# Sheet1.net
KiCad netlist of a schematic drawn in Altium Designer
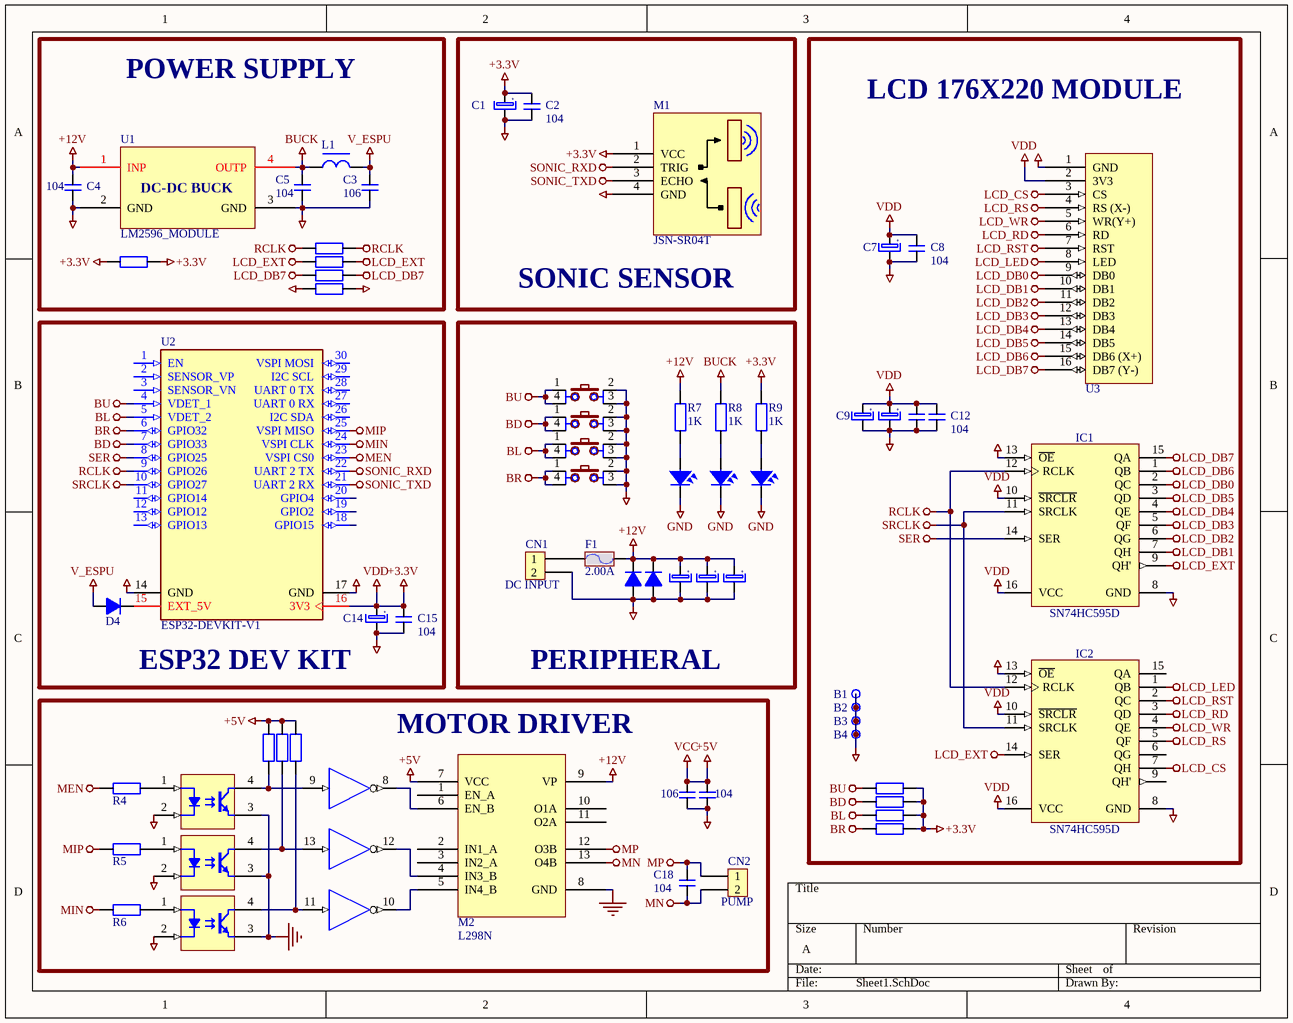
[diagram p0: Sheet1.SchDoc]

(export (version "E")
  (design (tool "Eeschema 10.0.6"))
  (components
    (comp (ref "B1")
      (value "Plated Hole")
      (footprint "MTG300_600")
      (description "Single Terminal Socket")
      (fields (field (name "PART NUMBER") "PLATED_HOLE3.0_PAD6.0") (field (name "AUTHOR") "CERN DEM JLC"))
      (libsource (lib "Eletro-mechanical") (part "Single Terminal Socket"))
    )
    (comp (ref "B2")
      (value "Plated Hole")
      (footprint "MTG300_600")
      (description "Single Terminal Socket")
      (fields (field (name "PART NUMBER") "PLATED_HOLE3.0_PAD6.0") (field (name "AUTHOR") "CERN DEM JLC"))
      (libsource (lib "Eletro-mechanical") (part "Single Terminal Socket"))
    )
    (comp (ref "B3")
      (value "Plated Hole")
      (footprint "MTG300_600")
      (description "Single Terminal Socket")
      (fields (field (name "PART NUMBER") "PLATED_HOLE3.0_PAD6.0") (field (name "AUTHOR") "CERN DEM JLC"))
      (libsource (lib "Eletro-mechanical") (part "Single Terminal Socket"))
    )
    (comp (ref "B4")
      (value "Plated Hole")
      (footprint "MTG300_600")
      (description "Single Terminal Socket")
      (fields (field (name "PART NUMBER") "PLATED_HOLE3.0_PAD6.0") (field (name "AUTHOR") "CERN DEM JLC"))
      (libsource (lib "Eletro-mechanical") (part "Single Terminal Socket"))
    )
    (comp (ref "C1")
      (value "220uF")
      (footprint "Cap-P-2.5/5")
      (description "Polarized capacitor")
      (libsource (lib "Library") (part "Cap-Pol-Dip"))
    )
    (comp (ref "C2")
      (value "104")
      (footprint "Cap-Non-150mil")
      (description "Non-polar capacitor")
      (libsource (lib "Library") (part "Cap-Non-Dip"))
    )
    (comp (ref "C3")
      (value "106")
      (footprint "CAP-SMD-0805")
      (description "Non-polar capacitor")
      (libsource (lib "Library") (part "Cap-Non-SMD"))
    )
    (comp (ref "C4")
      (value "104")
      (footprint "Cap-Non-150mil")
      (description "Non-polar capacitor")
      (libsource (lib "Library") (part "Cap-Non-Dip"))
    )
    (comp (ref "C5")
      (value "104")
      (footprint "Cap-Non-150mil")
      (description "Non-polar capacitor")
      (libsource (lib "Library") (part "Cap-Non-Dip"))
    )
    (comp (ref "C6")
      (value "470uF")
      (footprint "Cap-P-3.8/6.3")
      (description "Polarized capacitor")
      (libsource (lib "Library") (part "Cap-Pol-Dip"))
    )
    (comp (ref "C7")
      (value "220uF")
      (footprint "Cap-P-2.5/5")
      (description "Polarized capacitor")
      (libsource (lib "Library") (part "Cap-Pol-Dip"))
    )
    (comp (ref "C8")
      (value "104")
      (footprint "Cap-Non-150mil")
      (description "Non-polar capacitor")
      (libsource (lib "Library") (part "Cap-Non-Dip"))
    )
    (comp (ref "C9")
      (value "220uF")
      (footprint "Cap-P-2.5/5")
      (description "Polarized capacitor")
      (libsource (lib "Library") (part "Cap-Pol-Dip"))
    )
    (comp (ref "C10")
      (value "220uF")
      (footprint "Cap-P-2.5/5")
      (description "Polarized capacitor")
      (libsource (lib "Library") (part "Cap-Pol-Dip"))
    )
    (comp (ref "C11")
      (value "104")
      (footprint "Cap-Non-150mil")
      (description "Non-polar capacitor")
      (libsource (lib "Library") (part "Cap-Non-Dip"))
    )
    (comp (ref "C12")
      (value "104")
      (footprint "Cap-Non-150mil")
      (description "Non-polar capacitor")
      (libsource (lib "Library") (part "Cap-Non-Dip"))
    )
    (comp (ref "C13")
      (value "470uF")
      (footprint "Cap-P-3.8/6.3")
      (description "Polarized capacitor")
      (libsource (lib "Library") (part "Cap-Pol-Dip"))
    )
    (comp (ref "C14")
      (value "220uF")
      (footprint "Cap-P-2.5/5")
      (description "Polarized capacitor")
      (libsource (lib "Library") (part "Cap-Pol-Dip"))
    )
    (comp (ref "C15")
      (value "104")
      (footprint "Cap-Non-150mil")
      (description "Non-polar capacitor")
      (libsource (lib "Library") (part "Cap-Non-Dip"))
    )
    (comp (ref "C16")
      (value "106")
      (footprint "CAP-SMD-0805")
      (description "Non-polar capacitor")
      (libsource (lib "Library") (part "Cap-Non-SMD"))
    )
    (comp (ref "C17")
      (value "104")
      (footprint "CAP-SMD-0805")
      (description "Non-polar capacitor")
      (libsource (lib "Library") (part "Cap-Non-SMD"))
    )
    (comp (ref "C18")
      (value "104")
      (footprint "CAP-SMD-0805")
      (description "Non-polar capacitor")
      (libsource (lib "Library") (part "Cap-Non-Dip"))
    )
    (comp (ref "C19")
      (value "470uF")
      (footprint "Cap-P-3.8/6.3")
      (description "Polarized capacitor")
      (libsource (lib "Library") (part "Cap-Pol-Dip"))
    )
    (comp (ref "CN1") (value "DC INPUT") (footprint "KF2/5.08") (libsource (lib "Library") (part "KF 2")))
    (comp (ref "CN2") (value "PUMP") (footprint "KF2/5.08") (libsource (lib "") (part "KF 2_1")))
    (comp (ref "D1")
      (value "SS14")
      (footprint "SOD 106")
      (description "Diode SMD")
      (libsource (lib "Library") (part "Diode SMD"))
    )
    (comp (ref "D2")
      (value "SS14")
      (footprint "SOD 106")
      (description "Diode SMD")
      (libsource (lib "Library") (part "Diode SMD"))
    )
    (comp (ref "D4")
      (value "SS14")
      (footprint "SOD 106")
      (description "Diode SMD")
      (libsource (lib "Library") (part "Diode SMD"))
    )
    (comp (ref "F1") (value "2.00A") (footprint "Fuse-Dip1") (libsource (lib "Library") (part "Fuse Dip")))
    (comp (ref "IC1")
      (value "SN74HC595D")
      (footprint "SOIC127P600X175-16N")
      (description "8-Bit Shift Register With 3-State Output Register")
      (fields (field (name "MANUFACTURER") "TEXAS INSTRUMENTS") (field (name "AUTHOR") "CERN DEM JLC"))
      (libsource (lib "ICs And Semiconductors") (part "74595"))
    )
    (comp (ref "IC2")
      (value "SN74HC595D")
      (footprint "SOIC127P600X175-16N")
      (description "8-Bit Shift Register With 3-State Output Register")
      (fields (field (name "MANUFACTURER") "TEXAS INSTRUMENTS") (field (name "AUTHOR") "CERN DEM JLC"))
      (libsource (lib "ICs And Semiconductors") (part "74595"))
    )
    (comp (ref "IC3")
      (value "FOD817DSD")
      (footprint "DIP4")
      (description "Single Optocoupler")
      (fields (field (name "MANUFACTURER") "FAIRCHILD SEMICONDUCTOR") (field (name "AUTHOR") "CERN DEM JLC"))
      (libsource (lib "ICs And Semiconductors") (part "Optocoupler Type7"))
    )
    (comp (ref "IC4")
      (value "FOD817DSD")
      (footprint "DIP4")
      (description "Single Optocoupler")
      (fields (field (name "MANUFACTURER") "FAIRCHILD SEMICONDUCTOR") (field (name "AUTHOR") "CERN DEM JLC"))
      (libsource (lib "ICs And Semiconductors") (part "Optocoupler Type7"))
    )
    (comp (ref "IC5")
      (value "FOD817DSD")
      (footprint "DIP4")
      (description "Single Optocoupler")
      (fields (field (name "MANUFACTURER") "FAIRCHILD SEMICONDUCTOR") (field (name "AUTHOR") "CERN DEM JLC"))
      (libsource (lib "ICs And Semiconductors") (part "Optocoupler Type7"))
    )
    (comp (ref "IC6")
      (value "74HC14D")
      (footprint "SOIC127P600X175-14N")
      (description "Hex Schmitt-Trigger Inverter")
      (fields (field (name "MANUFACTURER") "NXP SEMICONDUCTORS") (field (name "AUTHOR") "CERN DEM JLC"))
      (libsource (lib "ICs And Semiconductors") (part "7414"))
    )
    (comp (ref "L1")
      (value "470uH")
      (footprint "L-DIP-M-5.3")
      (description "Inductor")
      (libsource (lib "Library") (part "IND-DIP-1"))
    )
    (comp (ref "LED1") (value "POWER") (footprint "LED-0805") (libsource (lib "Library") (part "LED_SMD")))
    (comp (ref "LED2") (value "ESP-5.0V") (footprint "LED-0805") (libsource (lib "Library") (part "LED_SMD")))
    (comp (ref "LED3") (value "ESP-3.3V") (footprint "LED-0805") (libsource (lib "Library") (part "LED_SMD")))
    (comp (ref "M1")
      (value "JSN-SR04T")
      (footprint "JSN-SR04T")
      (libsource (lib "TOAN_VERSION_1_0") (part "JSN-SR04T"))
    )
    (comp (ref "M2")
      (value "L298N")
      (footprint "L298N_MODULE")
      (libsource (lib "TOAN_VERSION_1_0") (part "L298N"))
    )
    (comp (ref "R1")
      (value "1K")
      (footprint "RES-SMD-0805")
      (description "Resistor 1/4W")
      (libsource (lib "Library") (part "Res 1/4W"))
    )
    (comp (ref "R2")
      (value "1K")
      (footprint "RES-SMD-0805")
      (description "Resistor 1/4W")
      (libsource (lib "Library") (part "Res 1/4W"))
    )
    (comp (ref "R3")
      (value "1K")
      (footprint "RES-SMD-0805")
      (description "Resistor 1/4W")
      (libsource (lib "Library") (part "Res 1/4W"))
    )
    (comp (ref "R4")
      (value "1K")
      (footprint "RES-SMD-0805")
      (description "Resistor 1/4W")
      (libsource (lib "Library") (part "Res 1/4W"))
    )
    (comp (ref "R5")
      (value "1K")
      (footprint "RES-SMD-0805")
      (description "Resistor 1/4W")
      (libsource (lib "Library") (part "Res 1/4W"))
    )
    (comp (ref "R6")
      (value "1K")
      (footprint "RES-SMD-0805")
      (description "Resistor 1/4W")
      (libsource (lib "Library") (part "Res 1/4W"))
    )
    (comp (ref "R7")
      (value "1K")
      (footprint "RES-SMD-0805")
      (description "Resistor 1/4W")
      (libsource (lib "Library") (part "Res 1/4W"))
    )
    (comp (ref "R8")
      (value "1K")
      (footprint "RES-SMD-0805")
      (description "Resistor 1/4W")
      (libsource (lib "Library") (part "Res 1/4W"))
    )
    (comp (ref "R9")
      (value "1K")
      (footprint "RES-SMD-0805")
      (description "Resistor 1/4W")
      (libsource (lib "Library") (part "Res 1/4W"))
    )
    (comp (ref "R13")
      (value "0R")
      (footprint "RES-SMD-0805")
      (description "Resistor SMD")
      (libsource (lib "Library") (part "Res SMD"))
    )
    (comp (ref "R14")
      (value "0R")
      (footprint "RES-SMD-0805")
      (description "Resistor SMD")
      (libsource (lib "Library") (part "Res SMD"))
    )
    (comp (ref "R15")
      (value "0R")
      (footprint "RES-SMD-0805")
      (description "Resistor SMD")
      (libsource (lib "Library") (part "Res SMD"))
    )
    (comp (ref "R16")
      (value "0R")
      (footprint "RES-SMD-1206")
      (description "Resistor SMD")
      (libsource (lib "Library") (part "Res SMD"))
    )
    (comp (ref "R21")
      (value "1K")
      (footprint "RES-SMD-0805")
      (description "Resistor 1/4W")
      (libsource (lib "Library") (part "Res 1/4W"))
    )
    (comp (ref "R22")
      (value "1K")
      (footprint "RES-SMD-0805")
      (description "Resistor 1/4W")
      (libsource (lib "Library") (part "Res 1/4W"))
    )
    (comp (ref "R23")
      (value "1K")
      (footprint "RES-SMD-0805")
      (description "Resistor 1/4W")
      (libsource (lib "Library") (part "Res 1/4W"))
    )
    (comp (ref "R24")
      (value "1K")
      (footprint "RES-SMD-0805")
      (description "Resistor 1/4W")
      (libsource (lib "Library") (part "Res 1/4W"))
    )
    (comp (ref "R27")
      (value "0R")
      (footprint "RES-SMD-1206")
      (description "Resistor 1/4W")
      (libsource (lib "Library") (part "Res 1/4W"))
    )
    (comp (ref "SW1")
      (value "UP")
      (footprint "Button-Dip4/6x6")
      (description "Switch button 4 pin")
      (libsource (lib "Library") (part "Button-4"))
    )
    (comp (ref "SW2")
      (value "DOWN")
      (footprint "Button-Dip4/6x6")
      (description "Switch button 4 pin")
      (libsource (lib "Library") (part "Button-4"))
    )
    (comp (ref "SW3")
      (value "LEFT")
      (footprint "Button-Dip4/6x6")
      (description "Switch button 4 pin")
      (libsource (lib "Library") (part "Button-4"))
    )
    (comp (ref "SW4")
      (value "RIGHT")
      (footprint "Button-Dip4/6x6")
      (description "Switch button 4 pin")
      (libsource (lib "Library") (part "Button-4"))
    )
    (comp (ref "U1")
      (value "LM2596_MODULE")
      (footprint "LM2596_MODULE")
      (libsource (lib "TOAN_VERSION_1_0") (part "LM2596_MODULE"))
    )
    (comp (ref "U2")
      (value "ESP32-DEVKIT-V1")
      (footprint "MODULE_ESP32-DEVKITC-32D")
      (fields (field (name "MF") "Espressif Systems") (field (name "MP") "ESP32-DEVKITC-32D"))
      (libsource (lib "TOAN_VERSION_1_0") (part "ESP32-DEVKIT-V1"))
    )
    (comp (ref "U3")
      (value "ST7775R_2.0")
      (footprint "LCD_176X220_MODULE")
      (libsource (lib "TOAN_VERSION_1_0") (part "LCD_176x220_ST7775R"))
    )
  )
  (nets
    (net (code "1") (name "+3.3V") (class "Default")
      (node (ref "C1") (pin "1") (pinfunction "1_1") (pintype "passive"))
      (node (ref "C10") (pin "1") (pinfunction "1_1") (pintype "passive"))
      (node (ref "C11") (pin "2") (pinfunction "2_2") (pintype "passive"))
      (node (ref "C12") (pin "2") (pinfunction "2_2") (pintype "passive"))
      (node (ref "C14") (pin "1") (pinfunction "1_1") (pintype "passive"))
      (node (ref "C15") (pin "2") (pinfunction "2_2") (pintype "passive"))
      (node (ref "C2") (pin "2") (pinfunction "2_2") (pintype "passive"))
      (node (ref "C7") (pin "1") (pinfunction "1_1") (pintype "passive"))
      (node (ref "C8") (pin "2") (pinfunction "2_2") (pintype "passive"))
      (node (ref "C9") (pin "1") (pinfunction "1_1") (pintype "passive"))
      (node (ref "IC1") (pin "10") (pinfunction "~{SRCLR}_10") (pintype "input"))
      (node (ref "IC1") (pin "16") (pinfunction "VCC_16") (pintype "power_in"))
      (node (ref "IC2") (pin "10") (pinfunction "~{SRCLR}_10") (pintype "input"))
      (node (ref "IC2") (pin "16") (pinfunction "VCC_16") (pintype "power_in"))
      (node (ref "M1") (pin "1") (pinfunction "VCC_1") (pintype "passive"))
      (node (ref "R21") (pin "1") (pinfunction "1_1") (pintype "passive"))
      (node (ref "R22") (pin "1") (pinfunction "1_1") (pintype "passive"))
      (node (ref "R23") (pin "1") (pinfunction "1_1") (pintype "passive"))
      (node (ref "R24") (pin "1") (pinfunction "1_1") (pintype "passive"))
      (node (ref "R27") (pin "1") (pinfunction "1_1") (pintype "passive"))
      (node (ref "R27") (pin "2") (pinfunction "2_2") (pintype "passive"))
      (node (ref "R9") (pin "2") (pinfunction "2_2") (pintype "passive"))
      (node (ref "U2") (pin "16") (pinfunction "3V3_16") (pintype "power_in"))
      (node (ref "U3") (pin "2") (pinfunction "3V3_2") (pintype "power_in"))
    )
    (net (code "2") (name "+5V") (class "Default")
      (node (ref "C16") (pin "2") (pinfunction "2_2") (pintype "passive"))
      (node (ref "C17") (pin "2") (pinfunction "2_2") (pintype "passive"))
      (node (ref "IC6") (pin "14") (pinfunction "VCC_14") (pintype "power_in"))
      (node (ref "M2") (pin "7") (pinfunction "VCC_7") (pintype "passive"))
      (node (ref "R1") (pin "2") (pinfunction "2_2") (pintype "passive"))
      (node (ref "R2") (pin "2") (pinfunction "2_2") (pintype "passive"))
      (node (ref "R3") (pin "2") (pinfunction "2_2") (pintype "passive"))
    )
    (net (code "3") (name "+12V") (class "Default")
      (node (ref "C13") (pin "1") (pinfunction "1_1") (pintype "passive"))
      (node (ref "C19") (pin "1") (pinfunction "1_1") (pintype "passive"))
      (node (ref "C4") (pin "1") (pinfunction "1_1") (pintype "passive"))
      (node (ref "C6") (pin "1") (pinfunction "1_1") (pintype "passive"))
      (node (ref "D1") (pin "2") (pinfunction "K_2") (pintype "passive"))
      (node (ref "D2") (pin "2") (pinfunction "K_2") (pintype "passive"))
      (node (ref "F1") (pin "2") (pinfunction "2_2") (pintype "passive"))
      (node (ref "M2") (pin "9") (pinfunction "VP_9") (pintype "passive"))
      (node (ref "R7") (pin "2") (pinfunction "2_2") (pintype "passive"))
      (node (ref "U1") (pin "1") (pinfunction "INP_1") (pintype "power_in"))
    )
    (net (code "4") (name "BD") (class "Default")
      (node (ref "R24") (pin "2") (pinfunction "2_2") (pintype "passive"))
      (node (ref "SW2") (pin "1") (pintype "passive"))
      (node (ref "SW2") (pin "4") (pinfunction "4_4") (pintype "passive"))
      (node (ref "U2") (pin "7") (pinfunction "GPIO33_7") (pintype "bidirectional"))
    )
    (net (code "5") (name "BL") (class "Default")
      (node (ref "R22") (pin "2") (pinfunction "2_2") (pintype "passive"))
      (node (ref "SW3") (pin "1") (pintype "passive"))
      (node (ref "SW3") (pin "4") (pinfunction "4_4") (pintype "passive"))
      (node (ref "U2") (pin "5") (pinfunction "VDET_2_5") (pintype "input"))
    )
    (net (code "6") (name "BR") (class "Default")
      (node (ref "R21") (pin "2") (pinfunction "2_2") (pintype "passive"))
      (node (ref "SW4") (pin "1") (pintype "passive"))
      (node (ref "SW4") (pin "4") (pinfunction "4_4") (pintype "passive"))
      (node (ref "U2") (pin "6") (pinfunction "GPIO32_6") (pintype "bidirectional"))
    )
    (net (code "7") (name "BU") (class "Default")
      (node (ref "R23") (pin "2") (pinfunction "2_2") (pintype "passive"))
      (node (ref "SW1") (pin "1") (pintype "passive"))
      (node (ref "SW1") (pin "4") (pinfunction "4_4") (pintype "passive"))
      (node (ref "U2") (pin "4") (pinfunction "VDET_1_4") (pintype "input"))
    )
    (net (code "8") (name "BUCK") (class "Default")
      (node (ref "C5") (pin "1") (pinfunction "1_1") (pintype "passive"))
      (node (ref "L1") (pin "1") (pinfunction "1_1") (pintype "passive"))
      (node (ref "R8") (pin "2") (pinfunction "2_2") (pintype "passive"))
      (node (ref "U1") (pin "4") (pinfunction "OUTP_4") (pintype "power_in"))
    )
    (net (code "9") (name "GND") (class "Default")
      (node (ref "B1") (pin "1") (pinfunction "1_1") (pintype "bidirectional"))
      (node (ref "B2") (pin "1") (pinfunction "1_1") (pintype "bidirectional"))
      (node (ref "B3") (pin "1") (pinfunction "1_1") (pintype "bidirectional"))
      (node (ref "B4") (pin "1") (pinfunction "1_1") (pintype "bidirectional"))
      (node (ref "C1") (pin "2") (pinfunction "2_2") (pintype "passive"))
      (node (ref "C10") (pin "2") (pinfunction "2_2") (pintype "passive"))
      (node (ref "C11") (pin "1") (pinfunction "1_1") (pintype "passive"))
      (node (ref "C12") (pin "1") (pinfunction "1_1") (pintype "passive"))
      (node (ref "C13") (pin "2") (pinfunction "2_2") (pintype "passive"))
      (node (ref "C14") (pin "2") (pinfunction "2_2") (pintype "passive"))
      (node (ref "C15") (pin "1") (pinfunction "1_1") (pintype "passive"))
      (node (ref "C16") (pin "1") (pinfunction "1_1") (pintype "passive"))
      (node (ref "C17") (pin "1") (pinfunction "1_1") (pintype "passive"))
      (node (ref "C19") (pin "2") (pinfunction "2_2") (pintype "passive"))
      (node (ref "C2") (pin "1") (pinfunction "1_1") (pintype "passive"))
      (node (ref "C3") (pin "1") (pinfunction "1_1") (pintype "passive"))
      (node (ref "C4") (pin "2") (pinfunction "2_2") (pintype "passive"))
      (node (ref "C5") (pin "2") (pinfunction "2_2") (pintype "passive"))
      (node (ref "C6") (pin "2") (pinfunction "2_2") (pintype "passive"))
      (node (ref "C7") (pin "2") (pinfunction "2_2") (pintype "passive"))
      (node (ref "C8") (pin "1") (pinfunction "1_1") (pintype "passive"))
      (node (ref "C9") (pin "2") (pinfunction "2_2") (pintype "passive"))
      (node (ref "CN1") (pin "2") (pinfunction "2_2") (pintype "passive"))
      (node (ref "D1") (pin "1") (pinfunction "A_1") (pintype "passive"))
      (node (ref "D2") (pin "1") (pinfunction "A_1") (pintype "passive"))
      (node (ref "IC1") (pin "13") (pinfunction "~{OE}_13") (pintype "input"))
      (node (ref "IC1") (pin "8") (pinfunction "GND_8") (pintype "power_in"))
      (node (ref "IC2") (pin "13") (pinfunction "~{OE}_13") (pintype "input"))
      (node (ref "IC2") (pin "8") (pinfunction "GND_8") (pintype "power_in"))
      (node (ref "IC3") (pin "2") (pinfunction "C_2") (pintype "input"))
      (node (ref "IC3") (pin "3") (pinfunction "E_3") (pintype "open_emitter"))
      (node (ref "IC4") (pin "2") (pinfunction "C_2") (pintype "input"))
      (node (ref "IC4") (pin "3") (pinfunction "E_3") (pintype "open_emitter"))
      (node (ref "IC5") (pin "2") (pinfunction "C_2") (pintype "input"))
      (node (ref "IC5") (pin "3") (pinfunction "E_3") (pintype "open_emitter"))
      (node (ref "IC6") (pin "7") (pinfunction "GND_7") (pintype "power_in"))
      (node (ref "LED1") (pin "2") (pinfunction "2_2") (pintype "passive"))
      (node (ref "LED2") (pin "2") (pinfunction "2_2") (pintype "passive"))
      (node (ref "LED3") (pin "2") (pinfunction "2_2") (pintype "passive"))
      (node (ref "M1") (pin "4") (pinfunction "GND_4") (pintype "passive"))
      (node (ref "M2") (pin "8") (pinfunction "GND_8") (pintype "passive"))
      (node (ref "R16") (pin "1") (pinfunction "1_1") (pintype "passive"))
      (node (ref "R16") (pin "2") (pinfunction "2_2") (pintype "passive"))
      (node (ref "SW1") (pin "2") (pinfunction "2_2") (pintype "passive"))
      (node (ref "SW1") (pin "3") (pinfunction "3_3") (pintype "passive"))
      (node (ref "SW2") (pin "2") (pinfunction "2_2") (pintype "passive"))
      (node (ref "SW2") (pin "3") (pinfunction "3_3") (pintype "passive"))
      (node (ref "SW3") (pin "2") (pinfunction "2_2") (pintype "passive"))
      (node (ref "SW3") (pin "3") (pinfunction "3_3") (pintype "passive"))
      (node (ref "SW4") (pin "2") (pinfunction "2_2") (pintype "passive"))
      (node (ref "SW4") (pin "3") (pinfunction "3_3") (pintype "passive"))
      (node (ref "U1") (pin "2") (pinfunction "GND_2") (pintype "power_in"))
      (node (ref "U1") (pin "3") (pinfunction "GND_3") (pintype "power_in"))
      (node (ref "U2") (pin "14") (pinfunction "GND_14") (pintype "power_in"))
      (node (ref "U2") (pin "17") (pinfunction "GND_17") (pintype "power_in"))
      (node (ref "U3") (pin "1") (pinfunction "GND_1") (pintype "power_in"))
    )
    (net (code "10") (name "LCD_CS") (class "Default")
      (node (ref "IC2") (pin "7") (pinfunction "QH_7") (pintype "tri_state"))
      (node (ref "U3") (pin "3") (pinfunction "CS_3") (pintype "input"))
    )
    (net (code "11") (name "LCD_DB0") (class "Default")
      (node (ref "IC1") (pin "2") (pinfunction "QC_2") (pintype "tri_state"))
      (node (ref "U3") (pin "9") (pinfunction "DB0_9") (pintype "bidirectional"))
    )
    (net (code "12") (name "LCD_DB1") (class "Default")
      (node (ref "IC1") (pin "7") (pinfunction "QH_7") (pintype "tri_state"))
      (node (ref "U3") (pin "10") (pinfunction "DB1_10") (pintype "bidirectional"))
    )
    (net (code "13") (name "LCD_DB2") (class "Default")
      (node (ref "IC1") (pin "6") (pinfunction "QG_6") (pintype "tri_state"))
      (node (ref "U3") (pin "11") (pinfunction "DB2_11") (pintype "bidirectional"))
    )
    (net (code "14") (name "LCD_DB3") (class "Default")
      (node (ref "IC1") (pin "5") (pinfunction "QF_5") (pintype "tri_state"))
      (node (ref "U3") (pin "12") (pinfunction "DB3_12") (pintype "bidirectional"))
    )
    (net (code "15") (name "LCD_DB4") (class "Default")
      (node (ref "IC1") (pin "4") (pinfunction "QE_4") (pintype "tri_state"))
      (node (ref "U3") (pin "13") (pinfunction "DB4_13") (pintype "bidirectional"))
    )
    (net (code "16") (name "LCD_DB5") (class "Default")
      (node (ref "IC1") (pin "3") (pinfunction "QD_3") (pintype "tri_state"))
      (node (ref "U3") (pin "14") (pinfunction "DB5_14") (pintype "bidirectional"))
    )
    (net (code "17") (name "LCD_DB6") (class "Default")
      (node (ref "IC1") (pin "1") (pinfunction "QB_1") (pintype "tri_state"))
      (node (ref "U3") (pin "15") (pinfunction "DB6_(X+)_15") (pintype "bidirectional"))
    )
    (net (code "18") (name "LCD_DB7") (class "Default")
      (node (ref "IC1") (pin "15") (pinfunction "QA_15") (pintype "tri_state"))
      (node (ref "R15") (pin "1") (pinfunction "1_1") (pintype "passive"))
      (node (ref "R15") (pin "2") (pinfunction "2_2") (pintype "passive"))
      (node (ref "U3") (pin "16") (pinfunction "DB7_(Y-)_16") (pintype "bidirectional"))
    )
    (net (code "19") (name "LCD_EXT") (class "Default")
      (node (ref "IC1") (pin "9") (pinfunction "QH'_9") (pintype "output"))
      (node (ref "IC2") (pin "14") (pinfunction "SER_14") (pintype "input"))
      (node (ref "R14") (pin "1") (pinfunction "1_1") (pintype "passive"))
      (node (ref "R14") (pin "2") (pinfunction "2_2") (pintype "passive"))
    )
    (net (code "20") (name "LCD_LED") (class "Default")
      (node (ref "IC2") (pin "1") (pinfunction "QB_1") (pintype "tri_state"))
      (node (ref "U3") (pin "8") (pinfunction "LED_8") (pintype "input"))
    )
    (net (code "21") (name "LCD_RD") (class "Default")
      (node (ref "IC2") (pin "3") (pinfunction "QD_3") (pintype "tri_state"))
      (node (ref "U3") (pin "6") (pinfunction "RD_6") (pintype "input"))
    )
    (net (code "22") (name "LCD_RS") (class "Default")
      (node (ref "IC2") (pin "5") (pinfunction "QF_5") (pintype "tri_state"))
      (node (ref "U3") (pin "4") (pinfunction "RS_(X-)_4") (pintype "input"))
    )
    (net (code "23") (name "LCD_RST") (class "Default")
      (node (ref "IC2") (pin "2") (pinfunction "QC_2") (pintype "tri_state"))
      (node (ref "U3") (pin "7") (pinfunction "RST_7") (pintype "input"))
    )
    (net (code "24") (name "LCD_WR") (class "Default")
      (node (ref "IC2") (pin "4") (pinfunction "QE_4") (pintype "tri_state"))
      (node (ref "U3") (pin "5") (pinfunction "WR(Y+)_5") (pintype "input"))
    )
    (net (code "25") (name "MEN") (class "Default")
      (node (ref "R4") (pin "2") (pinfunction "2_2") (pintype "passive"))
      (node (ref "U2") (pin "23") (pinfunction "VSPI_CS0_23") (pintype "bidirectional"))
    )
    (net (code "26") (name "MIN") (class "Default")
      (node (ref "R6") (pin "2") (pinfunction "2_2") (pintype "passive"))
      (node (ref "U2") (pin "24") (pinfunction "VSPI_CLK_24") (pintype "bidirectional"))
    )
    (net (code "27") (name "MIP") (class "Default")
      (node (ref "R5") (pin "2") (pinfunction "2_2") (pintype "passive"))
      (node (ref "U2") (pin "25") (pinfunction "VSPI_MISO_25") (pintype "bidirectional"))
    )
    (net (code "28") (name "MN") (class "Default")
      (node (ref "C18") (pin "1") (pinfunction "1_1") (pintype "passive"))
      (node (ref "CN2") (pin "2") (pinfunction "2_2") (pintype "passive"))
      (node (ref "M2") (pin "13") (pinfunction "O4B_13") (pintype "passive"))
    )
    (net (code "29") (name "MP") (class "Default")
      (node (ref "C18") (pin "2") (pinfunction "2_2") (pintype "passive"))
      (node (ref "CN2") (pin "1") (pinfunction "1_1") (pintype "passive"))
      (node (ref "M2") (pin "12") (pinfunction "O3B_12") (pintype "passive"))
    )
    (net (code "30") (name "Net-(CN1-Pad1)") (class "Default")
      (node (ref "CN1") (pin "1") (pinfunction "1_1") (pintype "passive"))
      (node (ref "F1") (pin "1") (pinfunction "1_1") (pintype "passive"))
    )
    (net (code "31") (name "Net-(D4-K)") (class "Default")
      (node (ref "D4") (pin "2") (pinfunction "K_2") (pintype "passive"))
      (node (ref "U2") (pin "15") (pinfunction "EXT_5V_15") (pintype "power_in"))
    )
    (net (code "32") (name "Net-(IC3-A)") (class "Default")
      (node (ref "IC3") (pin "1") (pinfunction "A_1") (pintype "input"))
      (node (ref "R4") (pin "1") (pinfunction "1_1") (pintype "passive"))
    )
    (net (code "33") (name "Net-(IC4-A)") (class "Default")
      (node (ref "IC4") (pin "1") (pinfunction "A_1") (pintype "input"))
      (node (ref "R6") (pin "1") (pinfunction "1_1") (pintype "passive"))
    )
    (net (code "34") (name "Net-(IC5-A)") (class "Default")
      (node (ref "IC5") (pin "1") (pinfunction "A_1") (pintype "input"))
      (node (ref "R5") (pin "1") (pinfunction "1_1") (pintype "passive"))
    )
    (net (code "35") (name "Net-(IC6D-IN)") (class "Default")
      (node (ref "IC3") (pin "4") (pinfunction "C_4") (pintype "open_collector"))
      (node (ref "IC6") (pin "9") (pinfunction "IN_9") (pintype "input"))
      (node (ref "R1") (pin "1") (pinfunction "1_1") (pintype "passive"))
    )
    (net (code "36") (name "Net-(IC6D-OUT)") (class "Default")
      (node (ref "IC6") (pin "8") (pinfunction "OUT_8") (pintype "output"))
      (node (ref "M2") (pin "6") (pinfunction "EN_B_6") (pintype "passive"))
    )
    (net (code "37") (name "Net-(IC6E-IN)") (class "Default")
      (node (ref "IC4") (pin "4") (pinfunction "C_4") (pintype "open_collector"))
      (node (ref "IC6") (pin "11") (pinfunction "IN_11") (pintype "input"))
      (node (ref "R3") (pin "1") (pinfunction "1_1") (pintype "passive"))
    )
    (net (code "38") (name "Net-(IC6E-OUT)") (class "Default")
      (node (ref "IC6") (pin "10") (pinfunction "OUT_10") (pintype "output"))
      (node (ref "M2") (pin "5") (pinfunction "IN4_B_5") (pintype "passive"))
    )
    (net (code "39") (name "Net-(IC6F-IN)") (class "Default")
      (node (ref "IC5") (pin "4") (pinfunction "C_4") (pintype "open_collector"))
      (node (ref "IC6") (pin "13") (pinfunction "IN_13") (pintype "input"))
      (node (ref "R2") (pin "1") (pinfunction "1_1") (pintype "passive"))
    )
    (net (code "40") (name "Net-(IC6F-OUT)") (class "Default")
      (node (ref "IC6") (pin "12") (pinfunction "OUT_12") (pintype "output"))
      (node (ref "M2") (pin "4") (pinfunction "IN3_B_4") (pintype "passive"))
    )
    (net (code "41") (name "Net-(LED1-Pad1)") (class "Default")
      (node (ref "LED1") (pin "1") (pinfunction "1_1") (pintype "passive"))
      (node (ref "R7") (pin "1") (pinfunction "1_1") (pintype "passive"))
    )
    (net (code "42") (name "Net-(LED2-Pad1)") (class "Default")
      (node (ref "LED2") (pin "1") (pinfunction "1_1") (pintype "passive"))
      (node (ref "R8") (pin "1") (pinfunction "1_1") (pintype "passive"))
    )
    (net (code "43") (name "Net-(LED3-Pad1)") (class "Default")
      (node (ref "LED3") (pin "1") (pinfunction "1_1") (pintype "passive"))
      (node (ref "R9") (pin "1") (pinfunction "1_1") (pintype "passive"))
    )
    (net (code "44") (name "RCLK") (class "Default")
      (node (ref "IC1") (pin "12") (pinfunction "RCLK_12") (pintype "input"))
      (node (ref "IC2") (pin "12") (pinfunction "RCLK_12") (pintype "input"))
      (node (ref "R13") (pin "1") (pinfunction "1_1") (pintype "passive"))
      (node (ref "R13") (pin "2") (pinfunction "2_2") (pintype "passive"))
      (node (ref "U2") (pin "9") (pinfunction "GPIO26_9") (pintype "bidirectional"))
    )
    (net (code "45") (name "SER") (class "Default")
      (node (ref "IC1") (pin "14") (pinfunction "SER_14") (pintype "input"))
      (node (ref "U2") (pin "8") (pinfunction "GPIO25_8") (pintype "bidirectional"))
    )
    (net (code "46") (name "SONIC_RXD") (class "Default")
      (node (ref "M1") (pin "2") (pinfunction "TRIG_2") (pintype "passive"))
      (node (ref "U2") (pin "22") (pinfunction "UART_2_TX_22") (pintype "bidirectional"))
    )
    (net (code "47") (name "SONIC_TXD") (class "Default")
      (node (ref "M1") (pin "3") (pinfunction "ECHO_3") (pintype "passive"))
      (node (ref "U2") (pin "21") (pinfunction "UART_2_RX_21") (pintype "bidirectional"))
    )
    (net (code "48") (name "SRCLK") (class "Default")
      (node (ref "IC1") (pin "11") (pinfunction "SRCLK_11") (pintype "input"))
      (node (ref "IC2") (pin "11") (pinfunction "SRCLK_11") (pintype "input"))
      (node (ref "U2") (pin "10") (pinfunction "GPIO27_10") (pintype "bidirectional"))
    )
    (net (code "49") (name "V_ESPU") (class "Default")
      (node (ref "C3") (pin "2") (pinfunction "2_2") (pintype "passive"))
      (node (ref "D4") (pin "1") (pinfunction "A_1") (pintype "passive"))
      (node (ref "L1") (pin "2") (pinfunction "2_2") (pintype "passive"))
    )
    (net (code "50") (name "unconnected-(IC2-QA-Pad15)") (class "Default")
      (node (ref "IC2") (pin "15") (pinfunction "QA_15") (pintype "tri_state"))
    )
    (net (code "51") (name "unconnected-(IC2-QG-Pad6)") (class "Default")
      (node (ref "IC2") (pin "6") (pinfunction "QG_6") (pintype "tri_state"))
    )
    (net (code "52") (name "unconnected-(IC2-QH'-Pad9)") (class "Default")
      (node (ref "IC2") (pin "9") (pinfunction "QH'_9") (pintype "output"))
    )
    (net (code "53") (name "unconnected-(M2-EN_A-Pad1)") (class "Default")
      (node (ref "M2") (pin "1") (pinfunction "EN_A_1") (pintype "passive"))
    )
    (net (code "54") (name "unconnected-(M2-IN1_A-Pad2)") (class "Default")
      (node (ref "M2") (pin "2") (pinfunction "IN1_A_2") (pintype "passive"))
    )
    (net (code "55") (name "unconnected-(M2-IN2_A-Pad3)") (class "Default")
      (node (ref "M2") (pin "3") (pinfunction "IN2_A_3") (pintype "passive"))
    )
    (net (code "56") (name "unconnected-(M2-O1A-Pad10)") (class "Default")
      (node (ref "M2") (pin "10") (pinfunction "O1A_10") (pintype "passive"))
    )
    (net (code "57") (name "unconnected-(M2-O2A-Pad11)") (class "Default")
      (node (ref "M2") (pin "11") (pinfunction "O2A_11") (pintype "passive"))
    )
    (net (code "58") (name "unconnected-(U2-EN-Pad1)") (class "Default")
      (node (ref "U2") (pin "1") (pinfunction "EN_1") (pintype "input"))
    )
    (net (code "59") (name "unconnected-(U2-GPIO2-Pad19)") (class "Default")
      (node (ref "U2") (pin "19") (pinfunction "GPIO2_19") (pintype "bidirectional"))
    )
    (net (code "60") (name "unconnected-(U2-GPIO4-Pad20)") (class "Default")
      (node (ref "U2") (pin "20") (pinfunction "GPIO4_20") (pintype "bidirectional"))
    )
    (net (code "61") (name "unconnected-(U2-GPIO12-Pad12)") (class "Default")
      (node (ref "U2") (pin "12") (pinfunction "GPIO12_12") (pintype "bidirectional"))
    )
    (net (code "62") (name "unconnected-(U2-GPIO13-Pad13)") (class "Default")
      (node (ref "U2") (pin "13") (pinfunction "GPIO13_13") (pintype "bidirectional"))
    )
    (net (code "63") (name "unconnected-(U2-GPIO14-Pad11)") (class "Default")
      (node (ref "U2") (pin "11") (pinfunction "GPIO14_11") (pintype "bidirectional"))
    )
    (net (code "64") (name "unconnected-(U2-GPIO15-Pad18)") (class "Default")
      (node (ref "U2") (pin "18") (pinfunction "GPIO15_18") (pintype "bidirectional"))
    )
    (net (code "65") (name "unconnected-(U2-I2C_SCL-Pad29)") (class "Default")
      (node (ref "U2") (pin "29") (pinfunction "I2C_SCL_29") (pintype "bidirectional"))
    )
    (net (code "66") (name "unconnected-(U2-I2C_SDA-Pad26)") (class "Default")
      (node (ref "U2") (pin "26") (pinfunction "I2C_SDA_26") (pintype "bidirectional"))
    )
    (net (code "67") (name "unconnected-(U2-SENSOR_VN-Pad3)") (class "Default")
      (node (ref "U2") (pin "3") (pinfunction "SENSOR_VN_3") (pintype "input"))
    )
    (net (code "68") (name "unconnected-(U2-SENSOR_VP-Pad2)") (class "Default")
      (node (ref "U2") (pin "2") (pinfunction "SENSOR_VP_2") (pintype "input"))
    )
    (net (code "69") (name "unconnected-(U2-UART_0_RX-Pad27)") (class "Default")
      (node (ref "U2") (pin "27") (pinfunction "UART_0_RX_27") (pintype "bidirectional"))
    )
    (net (code "70") (name "unconnected-(U2-UART_0_TX-Pad28)") (class "Default")
      (node (ref "U2") (pin "28") (pinfunction "UART_0_TX_28") (pintype "bidirectional"))
    )
    (net (code "71") (name "unconnected-(U2-VSPI_MOSI-Pad30)") (class "Default")
      (node (ref "U2") (pin "30") (pinfunction "VSPI_MOSI_30") (pintype "bidirectional"))
    )
  )
)
